# GettingStarted.net
KiCad netlist of a schematic drawn in EAGLE
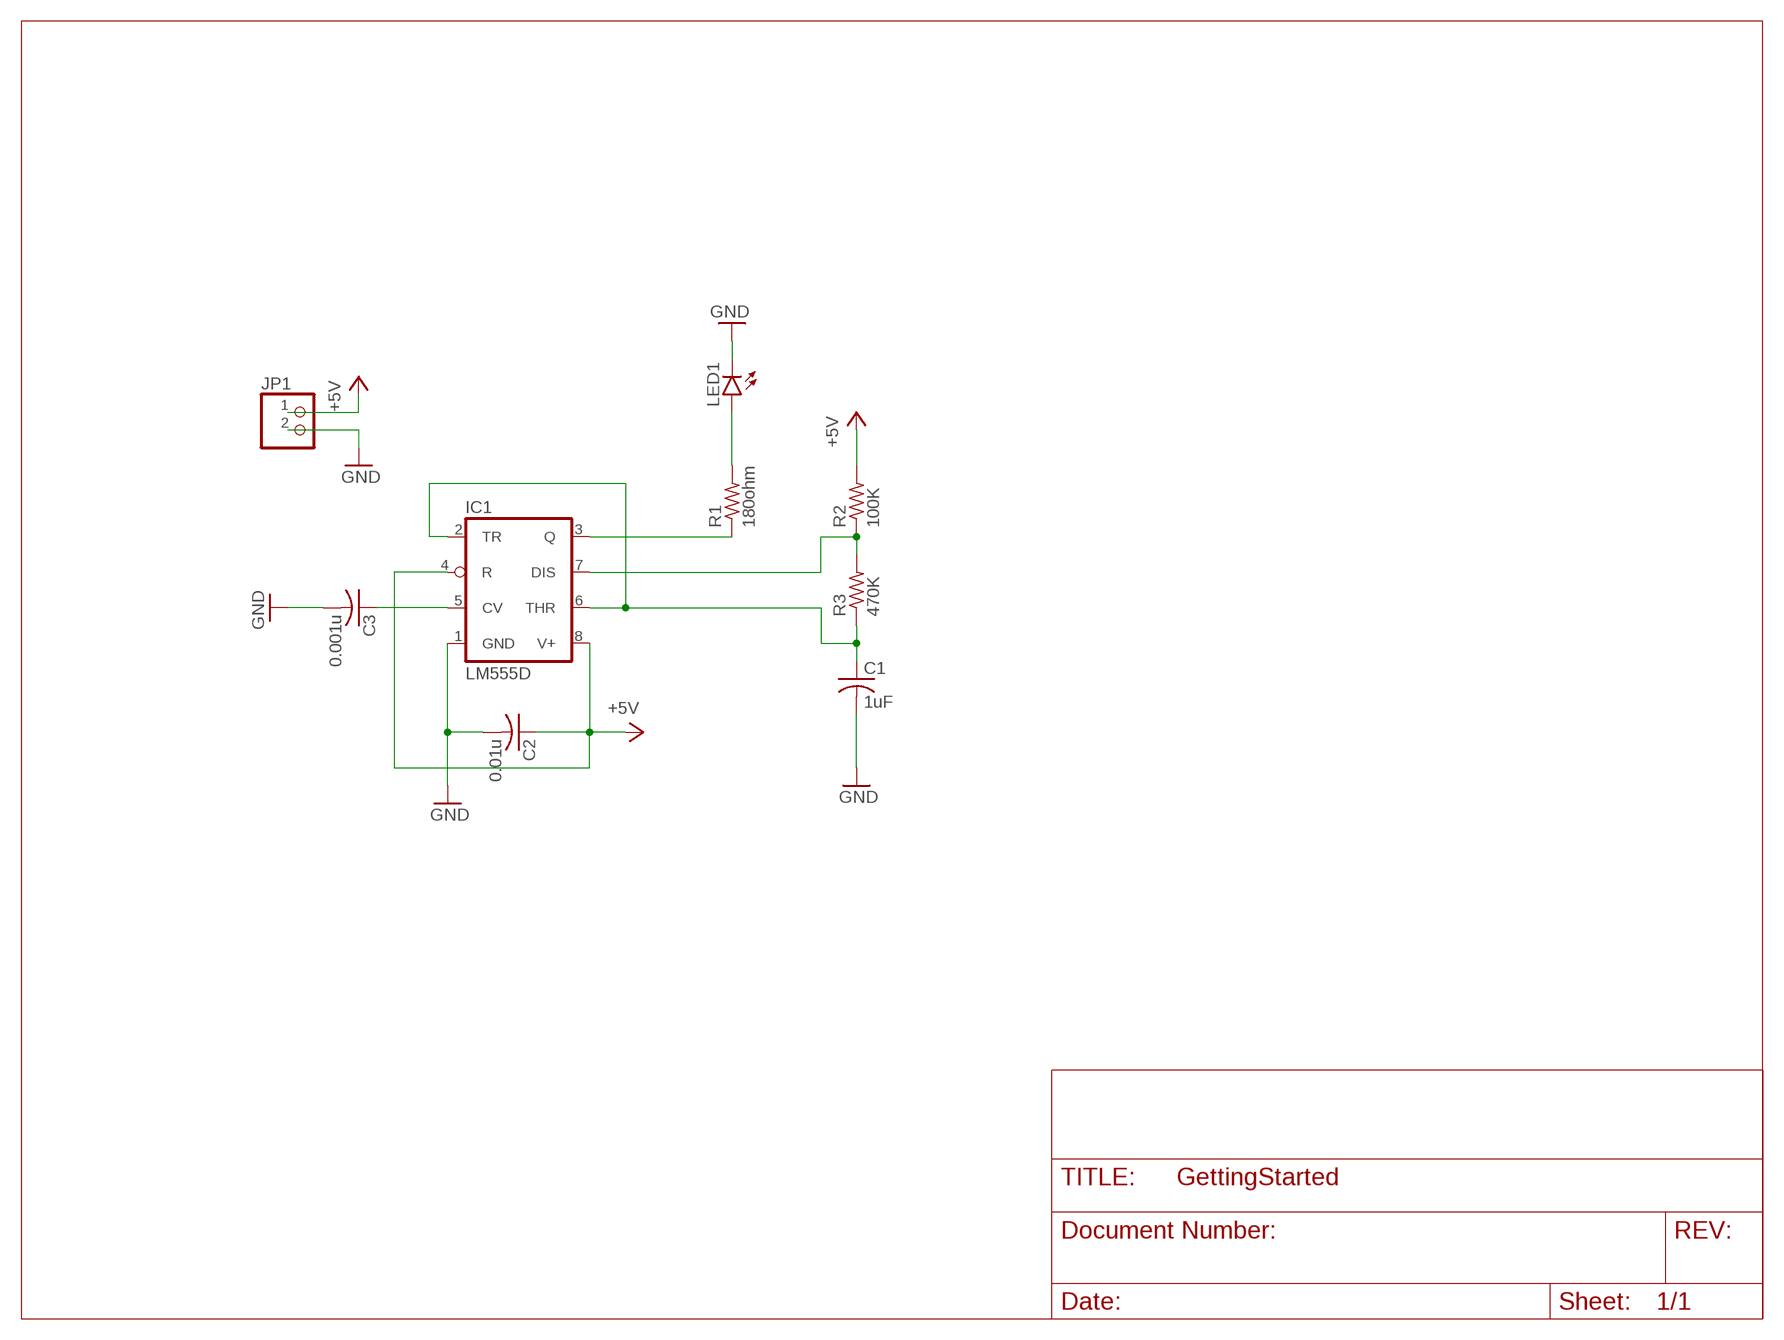
[diagram p0: schematic, sheet 1]

(export (version "E")
  (design (tool "Eeschema 10.0.6"))
  (components
    (comp (ref "C1")
      (value "1uF")
      (footprint "eagle-import:C0805")
      (libsource (lib "eagle-import") (part "C-USC0805"))
    )
    (comp (ref "C2")
      (value "0.01u")
      (footprint "eagle-import:C0805")
      (libsource (lib "eagle-import") (part "C-USC0805"))
    )
    (comp (ref "C3")
      (value "0.001u")
      (footprint "eagle-import:C0805")
      (libsource (lib "eagle-import") (part "C-USC0805"))
    )
    (comp (ref "IC1")
      (value "LM555D")
      (footprint "eagle-import:SO08")
      (libsource (lib "eagle-import") (part "555DLM"))
    )
    (comp (ref "JP1")
      (value "PINHD-1X2")
      (footprint "eagle-import:1X02")
      (libsource (lib "eagle-import") (part "PINHD-1X2"))
    )
    (comp (ref "LED1")
      (value "LED5MM")
      (footprint "eagle-import:LED5MM")
      (libsource (lib "eagle-import") (part "LED5MM"))
    )
    (comp (ref "R1")
      (value "180ohm")
      (footprint "eagle-import:R0805")
      (libsource (lib "eagle-import") (part "R-US_R0805"))
    )
    (comp (ref "R2")
      (value "100K")
      (footprint "eagle-import:R0805")
      (libsource (lib "eagle-import") (part "R-US_R0805"))
    )
    (comp (ref "R3")
      (value "470K")
      (footprint "eagle-import:R0805")
      (libsource (lib "eagle-import") (part "R-US_R0805"))
    )
  )
  (nets
    (net (code "1") (name "+5V") (class "Default")
      (node (ref "C2") (pin "1") (pinfunction "1_1") (pintype "passive"))
      (node (ref "IC1") (pin "4") (pinfunction "R_4") (pintype "input"))
      (node (ref "IC1") (pin "8") (pinfunction "V+_8") (pintype "power_in"))
      (node (ref "JP1") (pin "1") (pinfunction "1_1") (pintype "passive"))
      (node (ref "R2") (pin "2") (pinfunction "2_2") (pintype "passive"))
    )
    (net (code "2") (name "GND") (class "Default")
      (node (ref "C1") (pin "2") (pinfunction "2_2") (pintype "passive"))
      (node (ref "C2") (pin "2") (pinfunction "2_2") (pintype "passive"))
      (node (ref "C3") (pin "2") (pinfunction "2_2") (pintype "passive"))
      (node (ref "IC1") (pin "1") (pinfunction "GND_1") (pintype "power_in"))
      (node (ref "JP1") (pin "2") (pinfunction "2_2") (pintype "passive"))
      (node (ref "LED1") (pin "K") (pinfunction "C_K") (pintype "passive"))
    )
    (net (code "3") (name "Net-(IC1-CV)") (class "Default")
      (node (ref "C3") (pin "1") (pinfunction "1_1") (pintype "passive"))
      (node (ref "IC1") (pin "5") (pinfunction "CV_5") (pintype "input"))
    )
    (net (code "4") (name "Net-(IC1-DIS)") (class "Default")
      (node (ref "IC1") (pin "7") (pinfunction "DIS_7") (pintype "input"))
      (node (ref "R2") (pin "1") (pinfunction "1_1") (pintype "passive"))
      (node (ref "R3") (pin "2") (pinfunction "2_2") (pintype "passive"))
    )
    (net (code "5") (name "Net-(IC1-Q)") (class "Default")
      (node (ref "IC1") (pin "3") (pinfunction "Q_3") (pintype "output"))
      (node (ref "R1") (pin "1") (pinfunction "1_1") (pintype "passive"))
    )
    (net (code "6") (name "Net-(IC1-THR)") (class "Default")
      (node (ref "C1") (pin "1") (pinfunction "1_1") (pintype "passive"))
      (node (ref "IC1") (pin "2") (pinfunction "TR_2") (pintype "input"))
      (node (ref "IC1") (pin "6") (pinfunction "THR_6") (pintype "input"))
      (node (ref "R3") (pin "1") (pinfunction "1_1") (pintype "passive"))
    )
    (net (code "7") (name "Net-(LED1-PadA)") (class "Default")
      (node (ref "LED1") (pin "A") (pinfunction "A_A") (pintype "passive"))
      (node (ref "R1") (pin "2") (pinfunction "2_2") (pintype "passive"))
    )
  )
)
